# EFR32.net
KiCad netlist of a schematic drawn in Altium Designer
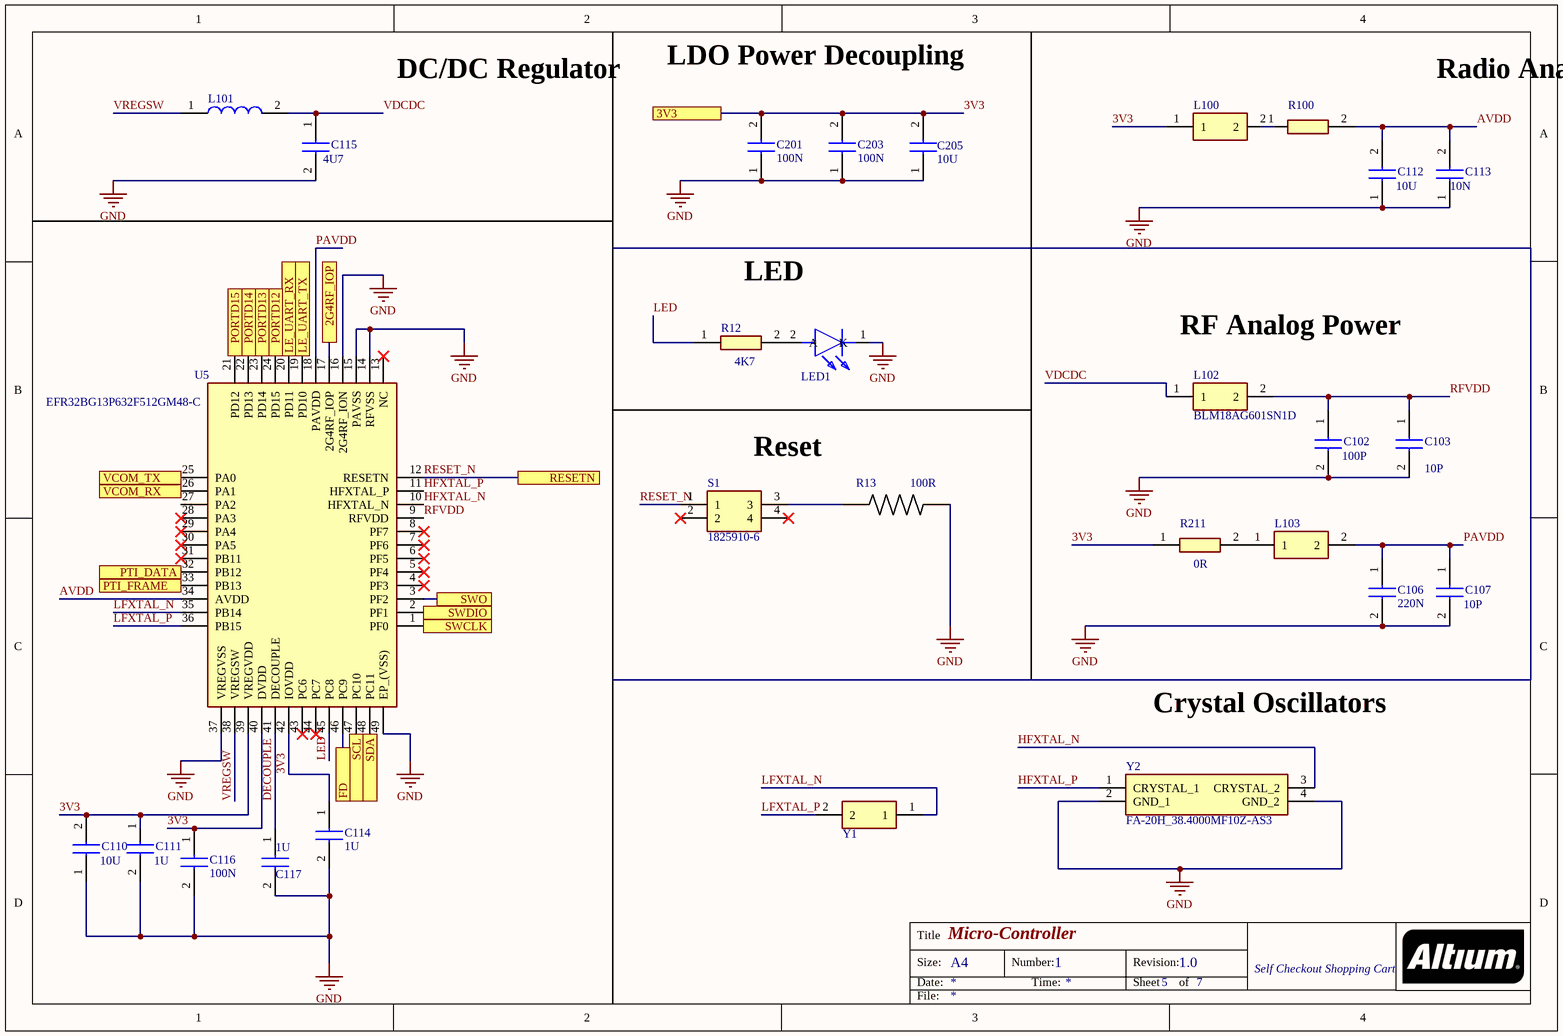
[diagram p0: EFR32.SchDoc]

(export (version "E")
  (design (tool "Eeschema 10.0.6"))
  (components
    (comp (ref "C102")
      (value "100P")
      (footprint "SamacSys:CAPC1608X90N")
      (description "Capacitor")
      (fields
        (field (name "MANUFACTURER_PART_NUMBER") "GCM1885C1H101JA16D")
        (field (name "MOUSER PART NUMBER") "81-GCM1885C1H101JA6D")
      )
      (libsource (lib "*") (part "GCM1885C1H101JA16D"))
    )
    (comp (ref "C103")
      (value "10P")
      (footprint "SamacSys:CAPC1608X90N")
      (description "Capacitor")
      (fields
        (field (name "MANUFACTURER_PART_NUMBER") "GRM1885C1H100JA01D")
        (field (name "MOUSER PART NUMBER") "81-GRM39C100D50")
      )
      (libsource (lib "*") (part "GRM1885C1H100JA01D"))
    )
    (comp (ref "C106")
      (value "220N")
      (footprint "SamacSys:CAPC1608X90N")
      (description "Capacitor")
      (fields
        (field (name "MANUFACTURER_PART_NUMBER") "CC0603KPX77BB224")
        (field (name "MOUSER PART NUMBER") "603-CC0603KPX77BB224")
      )
      (libsource (lib "*") (part "GRM188R71C224KA01D"))
    )
    (comp (ref "C107")
      (value "10P")
      (footprint "SamacSys:CAPC1608X90N")
      (description "Capacitor")
      (fields
        (field (name "MANUFACTURER_PART_NUMBER") "GRM1885C1H100JA01D")
        (field (name "MOUSER PART NUMBER") "81-GRM39C100D50")
      )
      (libsource (lib "*") (part "GRM1885C1H100JA01D"))
    )
    (comp (ref "C110")
      (value "10U")
      (footprint "SamacSys:CAPC1608X90N")
      (description "Capacitor")
      (fields
        (field (name "MANUFACTURER_PART_NUMBER") "GRM188R60J106ME84D")
        (field (name "MOUSER PART NUMBER") "81-GRM188R60J106ME4D")
      )
      (libsource (lib "*") (part "GRM188R60J106ME84D"))
    )
    (comp (ref "C111")
      (value "1U")
      (footprint "SamacSys:CAPC1608X90N")
      (description "Capacitor")
      (fields
        (field (name "MANUFACTURER_PART_NUMBER") "GRM188R61E105KAADD")
        (field (name "MOUSER PART NUMBER") "81-GRM188R61E105KADD")
      )
      (libsource (lib "*") (part "GRM188R61E105KAADD"))
    )
    (comp (ref "C112")
      (value "10U")
      (footprint "SamacSys:CAPC1608X90N")
      (description "Capacitor")
      (fields
        (field (name "MANUFACTURER_PART_NUMBER") "GRM188R60J106ME84D")
        (field (name "MOUSER PART NUMBER") "81-GRM188R60J106ME4D")
      )
      (libsource (lib "*") (part "GRM188R60J106ME84D"))
    )
    (comp (ref "C113")
      (value "10N")
      (footprint "Library_Cart:CAPC1608X90N")
      (description "Capacitor")
      (fields
        (field (name "MANUFACTURER_PART_NUMBER") "CC0603KRX7R7BB103")
        (field (name "MOUSER PART NUMBER") "603-CC603KRX7R7BB103")
      )
      (libsource (lib "*") (part "CC0603KRX7R7BB103"))
    )
    (comp (ref "C114")
      (value "1U")
      (footprint "SamacSys:CAPC1608X90N")
      (description "Capacitor")
      (fields
        (field (name "MANUFACTURER_PART_NUMBER") "GRM188R61E105KAADD")
        (field (name "MOUSER PART NUMBER") "81-GRM188R61E105KADD")
      )
      (libsource (lib "*") (part "GRM188R61E105KAADD"))
    )
    (comp (ref "C115")
      (value "4U7")
      (footprint "SamacSys:CAPC1608X90N")
      (description "Capacitor")
      (fields
        (field (name "MANUFACTURER_PART_NUMBER") "GRM188R61E475KE11D")
        (field (name "MOUSER PART NUMBER") "81-GRM188R61E475KE1D")
      )
      (libsource (lib "*") (part "GRM188R61E475KE11D"))
    )
    (comp (ref "C116")
      (value "100N")
      (footprint "SamacSys:CAPC1608X90N")
      (description "Capacitor")
      (fields
        (field (name "MANUFACTURER_PART_NUMBER") "GCM188R71C104KA37D")
        (field (name "MOUSER PART NUMBER") "81-GCM188R71C104KA7D")
      )
      (libsource (lib "*") (part "GCM188R71C104KA37D"))
    )
    (comp (ref "C117")
      (value "1U")
      (footprint "SamacSys:CAPC1608X90N")
      (description "Capacitor")
      (fields
        (field (name "MANUFACTURER_PART_NUMBER") "GRM188R61E105KAADD")
        (field (name "MOUSER PART NUMBER") "81-GRM188R61E105KADD")
      )
      (libsource (lib "*") (part "GRM188R61E105KAADD"))
    )
    (comp (ref "C201")
      (value "100N")
      (footprint "SamacSys:CAPC1608X90N")
      (description "Capacitor")
      (fields
        (field (name "MANUFACTURER_PART_NUMBER") "GCM188R71C104KA37D")
        (field (name "MOUSER PART NUMBER") "81-GCM188R71C104KA7D")
      )
      (libsource (lib "*") (part "GCM188R71C104KA37D"))
    )
    (comp (ref "C203")
      (value "100N")
      (footprint "SamacSys:CAPC1608X90N")
      (description "Capacitor")
      (fields
        (field (name "MANUFACTURER_PART_NUMBER") "GCM188R71C104KA37D")
        (field (name "MOUSER PART NUMBER") "81-GCM188R71C104KA7D")
      )
      (libsource (lib "*") (part "GCM188R71C104KA37D"))
    )
    (comp (ref "C205")
      (value "10U")
      (footprint "SamacSys:CAPC1608X90N")
      (description "Capacitor")
      (fields
        (field (name "MANUFACTURER_PART_NUMBER") "GRM188R61C106KAALJ")
        (field (name "MOUSER PART NUMBER") "81-GRM188R61C106KALJ")
      )
      (libsource (lib "*") (part "GRM188R61C106KAALJ"))
    )
    (comp (ref "L100")
      (value "74279266")
      (footprint "SamacSys:BEADC1608X100N")
      (description "Ferrite Bead")
      (fields (field (name "MOUSER PART NUMBER") "710-74279266") (field (name "RS PART NUMBER") "1241858P"))
      (libsource (lib "*") (part "74279266"))
    )
    (comp (ref "L101")
      (value "SRN3015-4R7M")
      (footprint "Library_Cart:INDPM3027X150N")
      (description "Inductor")
      (fields
        (field (name "MOUSER PART NUMBER") "652-SRN3015-4R7M")
        (field (name "RS PART NUMBER") "7435068")
      )
      (libsource (lib "*") (part "SRN3015-4R7M"))
    )
    (comp (ref "L102")
      (value "BLM18AG601SN1D")
      (footprint "SamacSys:BEADC1608X95N")
      (description "Filter")
      (fields (field (name "MOUSER PART NUMBER") "81-BLM11A601S") (field (name "RS PART NUMBER") "0110380"))
      (libsource (lib "*") (part "BLM18AG601SN1D"))
    )
    (comp (ref "L103")
      (value "BLM18AG601SN1D")
      (footprint "SamacSys:BEADC1608X95N")
      (description "Filter")
      (fields (field (name "MOUSER PART NUMBER") "81-BLM11A601S") (field (name "RS PART NUMBER") "0110380"))
      (libsource (lib "*") (part "BLM18AG601SN1D"))
    )
    (comp (ref "LED1")
      (value "SML-D12U1WT86")
      (footprint "SamacSys:LEDC1608X65N")
      (description "LED")
      (fields
        (field (name "MOUSER PART NUMBER") "755-SML-D12U1WT86")
        (field (name "RS PART NUMBER") "1332870P")
      )
      (libsource (lib "*") (part "SML-D12U1WT86"))
    )
    (comp (ref "R12")
      (value "4K7")
      (footprint "SamacSys:RESC1608X50N")
      (description "Resistor")
      (fields
        (field (name "MANUFACTURER_PART_NUMBER") "RCS06034K70FKEA")
        (field (name "MOUSER PART NUMBER") "71-RCS06034K70FKEA")
      )
      (libsource (lib "*") (part "RCS06034K70FKEA"))
    )
    (comp (ref "R13")
      (value "100R")
      (footprint "*RESC1608X55N")
      (description "Fixed Resistor CRGP 0603 100R 1%")
      (fields
        (field (name "MANUFACTURER_PART_NUMBER") "CRGP0603F100R")
        (field (name "DIGI-KEY PART NUMBER") "A130404CT-ND")
      )
      (libsource (lib "CRGP0603F100R") (part "CRGP0603F100R"))
    )
    (comp (ref "R100")
      (value "CRCW02011R00FXED")
      (footprint "SamacSys:RESC0603X28N")
      (description "Resistor")
      (fields (field (name "MOUSER PART NUMBER") "71-CRCW02011R00FXED"))
      (libsource (lib "*") (part "CRCW02011R00FXED"))
    )
    (comp (ref "R211")
      (value "0R")
      (footprint "SamacSys:RESC0603X28N")
      (description "Resistor")
      (fields
        (field (name "MANUFACTURER_PART_NUMBER") "CRCW02010000Z0ED")
        (field (name "MOUSER PART NUMBER") "71-CRCW02010000Z0ED")
      )
      (libsource (lib "*") (part "CRCW02010000Z0ED"))
    )
    (comp (ref "S1")
      (value "1825910-6")
      (footprint "SamacSys:1825910-6")
      (description "Switch")
      (fields (field (name "MOUSER PART NUMBER") "506-FSM4JH") (field (name "RS PART NUMBER") "4791413P"))
      (libsource (lib "*") (part "1825910-6"))
    )
    (comp (ref "U5")
      (value "EFR32BG13P632F512GM48-C")
      (footprint "*QFN40P600X600X100-49N")
      (description "Integrated Circuit")
      (fields (field (name "MOUSER PART NUMBER") "634-EFR32BG13P632-C"))
      (libsource (lib "EFR32BG13P632F512GM48") (part "EFR32BG13P632F512GM48-C"))
    )
    (comp (ref "Y1")
      (value "CM8V-T1A-32.768kHz-12.5pF-20PPM-TA-QC")
      (footprint "SamacSys:CM8V32768TA020125")
      (description "Crystal or Oscillator")
      (fields (field (name "MOUSER PART NUMBER") "428-201494-MC01"))
      (libsource (lib "*") (part "CM8V-T1A-32.768kHz-12.5pF-20PPM-TA-QC"))
    )
    (comp (ref "Y2")
      (value "FA-20H_38.4000MF10Z-AS3")
      (footprint "SamacSys:FA20H300000MF20XW")
      (description "Crystal or Oscillator")
      (fields
        (field (name "MANUFACTURER_PART_NUMBER") "FA-20H 38.4000MF10Z-AS3")
        (field (name "MOUSER PART NUMBER") "732-FA20H38.4F10ZAS3")
      )
      (libsource (lib "*") (part "FA-20H_38.4000MF10Z-AS3"))
    )
  )
  (nets
    (net (code "1") (name "/2G4RF_IOP") (class "Default")
      (node (ref "U5") (pin "17") (pinfunction "2G4RF_IOP_17") (pintype "passive"))
    )
    (net (code "2") (name "/3V3") (class "Default")
      (node (ref "C110") (pin "2") (pinfunction "2_2") (pintype "passive"))
      (node (ref "C111") (pin "1") (pinfunction "1_1") (pintype "passive"))
      (node (ref "C114") (pin "1") (pinfunction "1_1") (pintype "passive"))
      (node (ref "C116") (pin "1") (pinfunction "1_1") (pintype "passive"))
      (node (ref "C201") (pin "2") (pinfunction "2_2") (pintype "passive"))
      (node (ref "C203") (pin "2") (pinfunction "2_2") (pintype "passive"))
      (node (ref "C205") (pin "2") (pinfunction "2_2") (pintype "passive"))
      (node (ref "L100") (pin "1") (pinfunction "1_1") (pintype "passive"))
      (node (ref "R211") (pin "1") (pinfunction "1_1") (pintype "passive"))
      (node (ref "U5") (pin "39") (pinfunction "VREGVDD_39") (pintype "passive"))
      (node (ref "U5") (pin "40") (pinfunction "DVDD_40") (pintype "passive"))
      (node (ref "U5") (pin "42") (pinfunction "IOVDD_42") (pintype "passive"))
    )
    (net (code "3") (name "/AVDD") (class "Default")
      (node (ref "C112") (pin "2") (pinfunction "2_2") (pintype "passive"))
      (node (ref "C113") (pin "2") (pinfunction "2_2") (pintype "passive"))
      (node (ref "R100") (pin "2") (pinfunction "2_2") (pintype "passive"))
      (node (ref "U5") (pin "34") (pinfunction "AVDD_34") (pintype "passive"))
    )
    (net (code "4") (name "/DECOUPLE") (class "Default")
      (node (ref "C117") (pin "1") (pinfunction "1_1") (pintype "passive"))
      (node (ref "U5") (pin "41") (pinfunction "DECOUPLE_41") (pintype "passive"))
    )
    (net (code "5") (name "/FD") (class "Default")
      (node (ref "U5") (pin "46") (pinfunction "PC9_46") (pintype "passive"))
    )
    (net (code "6") (name "/HFXTAL_N") (class "Default")
      (node (ref "U5") (pin "10") (pinfunction "HFXTAL_N_10") (pintype "passive"))
      (node (ref "Y2") (pin "3") (pinfunction "CRYSTAL_2_3") (pintype "passive"))
    )
    (net (code "7") (name "/HFXTAL_P") (class "Default")
      (node (ref "U5") (pin "11") (pinfunction "HFXTAL_P_11") (pintype "passive"))
      (node (ref "Y2") (pin "1") (pinfunction "CRYSTAL_1_1") (pintype "passive"))
    )
    (net (code "8") (name "/LED") (class "Default")
      (node (ref "R12") (pin "1") (pinfunction "1_1") (pintype "passive"))
      (node (ref "U5") (pin "45") (pinfunction "PC8_45") (pintype "passive"))
    )
    (net (code "9") (name "/LE_UART_RX") (class "Default")
      (node (ref "U5") (pin "20") (pinfunction "PD11_20") (pintype "passive"))
    )
    (net (code "10") (name "/LE_UART_TX") (class "Default")
      (node (ref "U5") (pin "19") (pinfunction "PD10_19") (pintype "passive"))
    )
    (net (code "11") (name "/LFXTAL_N") (class "Default")
      (node (ref "U5") (pin "35") (pinfunction "PB14_35") (pintype "passive"))
      (node (ref "Y1") (pin "1") (pinfunction "1_1") (pintype "passive"))
    )
    (net (code "12") (name "/LFXTAL_P") (class "Default")
      (node (ref "U5") (pin "36") (pinfunction "PB15_36") (pintype "passive"))
      (node (ref "Y1") (pin "2") (pinfunction "2_2") (pintype "passive"))
    )
    (net (code "13") (name "/PAVDD") (class "Default")
      (node (ref "C106") (pin "1") (pinfunction "1_1") (pintype "passive"))
      (node (ref "C107") (pin "1") (pinfunction "1_1") (pintype "passive"))
      (node (ref "L103") (pin "2") (pinfunction "2_2") (pintype "passive"))
      (node (ref "U5") (pin "18") (pinfunction "PAVDD_18") (pintype "passive"))
    )
    (net (code "14") (name "/PORTD12") (class "Default")
      (node (ref "U5") (pin "24") (pinfunction "PD15_24") (pintype "passive"))
    )
    (net (code "15") (name "/PORTD13") (class "Default")
      (node (ref "U5") (pin "23") (pinfunction "PD14_23") (pintype "passive"))
    )
    (net (code "16") (name "/PORTD14") (class "Default")
      (node (ref "U5") (pin "22") (pinfunction "PD13_22") (pintype "passive"))
    )
    (net (code "17") (name "/PORTD15") (class "Default")
      (node (ref "U5") (pin "21") (pinfunction "PD12_21") (pintype "passive"))
    )
    (net (code "18") (name "/PTI_DATA") (class "Default")
      (node (ref "U5") (pin "32") (pinfunction "PB12_32") (pintype "passive"))
    )
    (net (code "19") (name "/PTI_FRAME") (class "Default")
      (node (ref "U5") (pin "33") (pinfunction "PB13_33") (pintype "passive"))
    )
    (net (code "20") (name "/RESET_N") (class "Default")
      (node (ref "S1") (pin "1") (pinfunction "1_1") (pintype "passive"))
      (node (ref "U5") (pin "12") (pinfunction "RESETN_12") (pintype "passive"))
    )
    (net (code "21") (name "/RFVDD") (class "Default")
      (node (ref "C102") (pin "1") (pinfunction "1_1") (pintype "passive"))
      (node (ref "C103") (pin "1") (pinfunction "1_1") (pintype "passive"))
      (node (ref "L102") (pin "2") (pinfunction "2_2") (pintype "passive"))
      (node (ref "U5") (pin "9") (pinfunction "RFVDD_9") (pintype "passive"))
    )
    (net (code "22") (name "/SCL") (class "Default")
      (node (ref "U5") (pin "47") (pinfunction "PC10_47") (pintype "passive"))
    )
    (net (code "23") (name "/SDA") (class "Default")
      (node (ref "U5") (pin "48") (pinfunction "PC11_48") (pintype "passive"))
    )
    (net (code "24") (name "/SWCLK") (class "Default")
      (node (ref "U5") (pin "1") (pinfunction "PF0_1") (pintype "passive"))
    )
    (net (code "25") (name "/SWDIO") (class "Default")
      (node (ref "U5") (pin "2") (pinfunction "PF1_2") (pintype "passive"))
    )
    (net (code "26") (name "/SWO") (class "Default")
      (node (ref "U5") (pin "3") (pinfunction "PF2_3") (pintype "passive"))
    )
    (net (code "27") (name "/VCOM_RX") (class "Default")
      (node (ref "U5") (pin "26") (pinfunction "PA1_26") (pintype "passive"))
    )
    (net (code "28") (name "/VCOM_TX") (class "Default")
      (node (ref "U5") (pin "25") (pinfunction "PA0_25") (pintype "passive"))
    )
    (net (code "29") (name "/VDCDC") (class "Default")
      (node (ref "C115") (pin "1") (pinfunction "1_1") (pintype "passive"))
      (node (ref "L101") (pin "2") (pinfunction "2_2") (pintype "passive"))
      (node (ref "L102") (pin "1") (pinfunction "1_1") (pintype "passive"))
    )
    (net (code "30") (name "/VREGSW") (class "Default")
      (node (ref "L101") (pin "1") (pinfunction "1_1") (pintype "passive"))
      (node (ref "U5") (pin "38") (pinfunction "VREGSW_38") (pintype "passive"))
    )
    (net (code "31") (name "GND") (class "Default")
      (node (ref "C102") (pin "2") (pinfunction "2_2") (pintype "passive"))
      (node (ref "C103") (pin "2") (pinfunction "2_2") (pintype "passive"))
      (node (ref "C106") (pin "2") (pinfunction "2_2") (pintype "passive"))
      (node (ref "C107") (pin "2") (pinfunction "2_2") (pintype "passive"))
      (node (ref "C110") (pin "1") (pinfunction "1_1") (pintype "passive"))
      (node (ref "C111") (pin "2") (pinfunction "2_2") (pintype "passive"))
      (node (ref "C112") (pin "1") (pinfunction "1_1") (pintype "passive"))
      (node (ref "C113") (pin "1") (pinfunction "1_1") (pintype "passive"))
      (node (ref "C114") (pin "2") (pinfunction "2_2") (pintype "passive"))
      (node (ref "C115") (pin "2") (pinfunction "2_2") (pintype "passive"))
      (node (ref "C116") (pin "2") (pinfunction "2_2") (pintype "passive"))
      (node (ref "C117") (pin "2") (pinfunction "2_2") (pintype "passive"))
      (node (ref "C201") (pin "1") (pinfunction "1_1") (pintype "passive"))
      (node (ref "C203") (pin "1") (pinfunction "1_1") (pintype "passive"))
      (node (ref "C205") (pin "1") (pinfunction "1_1") (pintype "passive"))
      (node (ref "LED1") (pin "1") (pinfunction "K_1") (pintype "passive"))
      (node (ref "R13") (pin "2") (pinfunction "2_2") (pintype "passive"))
      (node (ref "U5") (pin "14") (pinfunction "RFVSS_14") (pintype "passive"))
      (node (ref "U5") (pin "15") (pinfunction "PAVSS_15") (pintype "passive"))
      (node (ref "U5") (pin "16") (pinfunction "2G4RF_ION_16") (pintype "passive"))
      (node (ref "U5") (pin "37") (pinfunction "VREGVSS_37") (pintype "passive"))
      (node (ref "U5") (pin "49") (pinfunction "EP_(VSS)_49") (pintype "passive"))
      (node (ref "Y2") (pin "2") (pinfunction "GND_1_2") (pintype "power_in"))
      (node (ref "Y2") (pin "4") (pinfunction "GND_2_4") (pintype "power_in"))
    )
    (net (code "32") (name "Net-(L100-Pad2)") (class "Default")
      (node (ref "L100") (pin "2") (pinfunction "2_2") (pintype "passive"))
      (node (ref "R100") (pin "1") (pinfunction "1_1") (pintype "passive"))
    )
    (net (code "33") (name "Net-(L103-Pad1)") (class "Default")
      (node (ref "L103") (pin "1") (pinfunction "1_1") (pintype "passive"))
      (node (ref "R211") (pin "2") (pinfunction "2_2") (pintype "passive"))
    )
    (net (code "34") (name "Net-(LED1-A)") (class "Default")
      (node (ref "LED1") (pin "2") (pinfunction "A_2") (pintype "passive"))
      (node (ref "R12") (pin "2") (pinfunction "2_2") (pintype "passive"))
    )
    (net (code "35") (name "Net-(R13-Pad1)") (class "Default")
      (node (ref "R13") (pin "1") (pinfunction "1_1") (pintype "passive"))
      (node (ref "S1") (pin "3") (pinfunction "3_3") (pintype "passive"))
    )
    (net (code "36") (name "unconnected-(S1-Pad2)") (class "Default")
      (node (ref "S1") (pin "2") (pinfunction "2_2") (pintype "passive+no_connect"))
    )
    (net (code "37") (name "unconnected-(S1-Pad4)") (class "Default")
      (node (ref "S1") (pin "4") (pinfunction "4_4") (pintype "passive+no_connect"))
    )
    (net (code "38") (name "unconnected-(U5-NC-Pad13)") (class "Default")
      (node (ref "U5") (pin "13") (pinfunction "NC_13") (pintype "passive+no_connect"))
    )
    (net (code "39") (name "unconnected-(U5-PA2-Pad27)") (class "Default")
      (node (ref "U5") (pin "27") (pinfunction "PA2_27") (pintype "passive"))
    )
    (net (code "40") (name "unconnected-(U5-PA3-Pad28)") (class "Default")
      (node (ref "U5") (pin "28") (pinfunction "PA3_28") (pintype "passive+no_connect"))
    )
    (net (code "41") (name "unconnected-(U5-PA4-Pad29)") (class "Default")
      (node (ref "U5") (pin "29") (pinfunction "PA4_29") (pintype "passive+no_connect"))
    )
    (net (code "42") (name "unconnected-(U5-PA5-Pad30)") (class "Default")
      (node (ref "U5") (pin "30") (pinfunction "PA5_30") (pintype "passive+no_connect"))
    )
    (net (code "43") (name "unconnected-(U5-PB11-Pad31)") (class "Default")
      (node (ref "U5") (pin "31") (pinfunction "PB11_31") (pintype "passive+no_connect"))
    )
    (net (code "44") (name "unconnected-(U5-PC6-Pad43)") (class "Default")
      (node (ref "U5") (pin "43") (pinfunction "PC6_43") (pintype "passive+no_connect"))
    )
    (net (code "45") (name "unconnected-(U5-PC7-Pad44)") (class "Default")
      (node (ref "U5") (pin "44") (pinfunction "PC7_44") (pintype "passive+no_connect"))
    )
    (net (code "46") (name "unconnected-(U5-PF3-Pad4)") (class "Default")
      (node (ref "U5") (pin "4") (pinfunction "PF3_4") (pintype "passive+no_connect"))
    )
    (net (code "47") (name "unconnected-(U5-PF4-Pad5)") (class "Default")
      (node (ref "U5") (pin "5") (pinfunction "PF4_5") (pintype "passive+no_connect"))
    )
    (net (code "48") (name "unconnected-(U5-PF5-Pad6)") (class "Default")
      (node (ref "U5") (pin "6") (pinfunction "PF5_6") (pintype "passive+no_connect"))
    )
    (net (code "49") (name "unconnected-(U5-PF6-Pad7)") (class "Default")
      (node (ref "U5") (pin "7") (pinfunction "PF6_7") (pintype "passive+no_connect"))
    )
    (net (code "50") (name "unconnected-(U5-PF7-Pad8)") (class "Default")
      (node (ref "U5") (pin "8") (pinfunction "PF7_8") (pintype "passive+no_connect"))
    )
  )
)
